# Primjenjena_II.net
KiCad netlist of a schematic drawn in Altium Designer
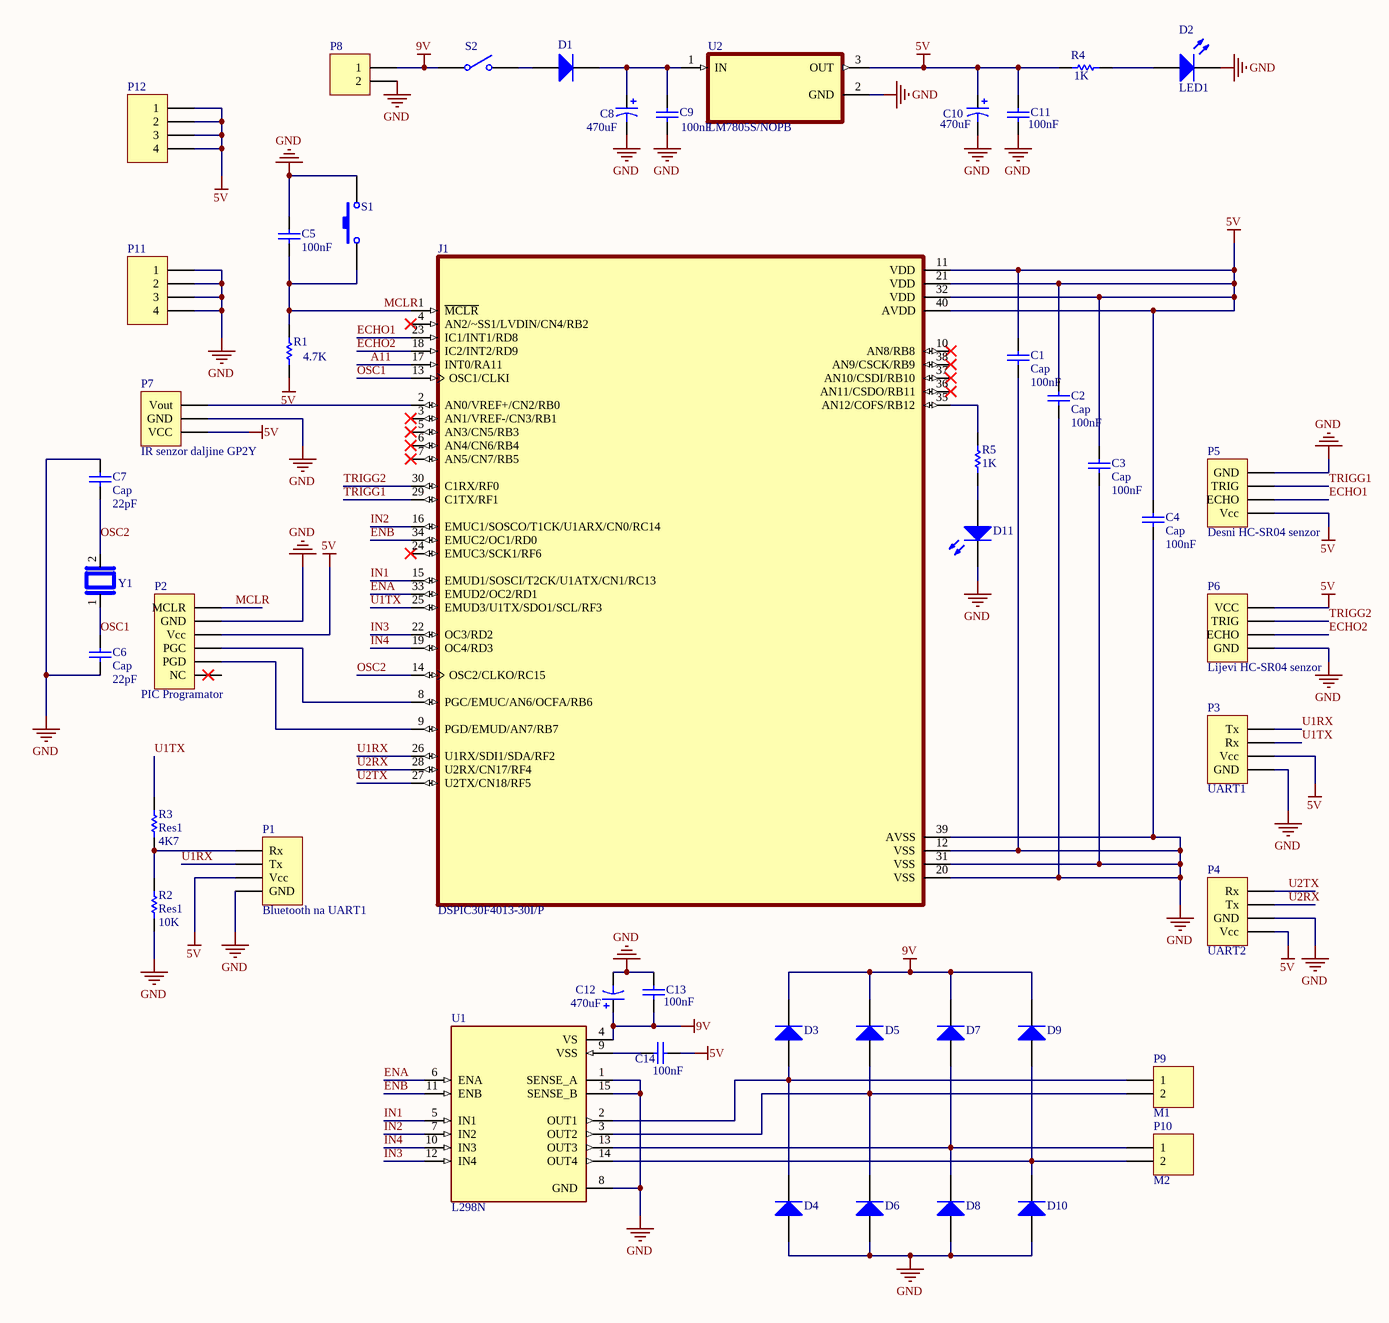
[diagram p0: Primjenjena_II.SchDoc]

(export (version "E")
  (design (tool "Eeschema 10.0.6"))
  (components
    (comp (ref "C1")
      (value "Cap")
      (footprint "RAD-0.1")
      (description "Capacitor")
      (fields (field (name "ALTIUM_VALUE") "100nF") (field (name "PUBLISHER") "Altium Limited"))
      (libsource (lib "Miscellaneous Devices") (part "Cap"))
    )
    (comp (ref "C2")
      (value "Cap")
      (footprint "RAD-0.1")
      (description "Capacitor")
      (fields (field (name "ALTIUM_VALUE") "100nF") (field (name "PUBLISHER") "Altium Limited"))
      (libsource (lib "Miscellaneous Devices") (part "Cap"))
    )
    (comp (ref "C3")
      (value "Cap")
      (footprint "RAD-0.1")
      (description "Capacitor")
      (fields (field (name "ALTIUM_VALUE") "100nF") (field (name "PUBLISHER") "Altium Limited"))
      (libsource (lib "Miscellaneous Devices") (part "Cap"))
    )
    (comp (ref "C4")
      (value "Cap")
      (footprint "RAD-0.1")
      (description "Capacitor")
      (fields (field (name "ALTIUM_VALUE") "100nF") (field (name "PUBLISHER") "Altium Limited"))
      (libsource (lib "Miscellaneous Devices") (part "Cap"))
    )
    (comp (ref "C5")
      (value "100nF")
      (footprint "RAD-0.1")
      (description "Capacitor")
      (fields (field (name "Comment") "Cap") (field (name "PUBLISHER") "Altium Limited"))
      (libsource (lib "Miscellaneous Devices") (part "Cap"))
    )
    (comp (ref "C6")
      (value "Cap")
      (footprint "RAD-0.1")
      (description "Capacitor")
      (fields (field (name "ALTIUM_VALUE") "22pF") (field (name "PUBLISHER") "Altium Limited"))
      (libsource (lib "Miscellaneous Devices") (part "Cap"))
    )
    (comp (ref "C7")
      (value "Cap")
      (footprint "RAD-0.1")
      (description "Capacitor")
      (fields (field (name "ALTIUM_VALUE") "22pF") (field (name "PUBLISHER") "Altium Limited"))
      (libsource (lib "Miscellaneous Devices") (part "Cap"))
    )
    (comp (ref "C8")
      (value "470uF")
      (footprint "Elektrolitski kondenzator")
      (description "Polarized Capacitor (Radial)")
      (fields (field (name "Comment") "Cap Pol1") (field (name "PUBLISHER") "Altium Limited"))
      (libsource (lib "Miscellaneous Devices") (part "Cap Pol1"))
    )
    (comp (ref "C9")
      (value "100nF")
      (footprint "RAD-0.1")
      (description "Capacitor")
      (fields (field (name "Comment") "Cap") (field (name "PUBLISHER") "Altium Limited"))
      (libsource (lib "Miscellaneous Devices") (part "Cap"))
    )
    (comp (ref "C10")
      (value "470uF")
      (footprint "Elektrolitski kondenzator")
      (description "Polarized Capacitor (Radial)")
      (fields (field (name "Comment") "Cap Pol1") (field (name "PUBLISHER") "Altium Limited"))
      (libsource (lib "Miscellaneous Devices") (part "Cap Pol1"))
    )
    (comp (ref "C11")
      (value "100nF")
      (footprint "RAD-0.1")
      (description "Capacitor")
      (fields (field (name "Comment") "Cap") (field (name "PUBLISHER") "Altium Limited"))
      (libsource (lib "Miscellaneous Devices") (part "Cap"))
    )
    (comp (ref "C12")
      (value "470uF")
      (footprint "Elektrolitski kondenzator")
      (description "Polarized Capacitor (Radial)")
      (fields (field (name "Comment") "Cap Pol1") (field (name "PUBLISHER") "Altium Limited"))
      (libsource (lib "Miscellaneous Devices") (part "Cap Pol1"))
    )
    (comp (ref "C13")
      (value "100nF")
      (footprint "RAD-0.1")
      (description "Capacitor")
      (fields (field (name "Comment") "Cap") (field (name "PUBLISHER") "Altium Limited"))
      (libsource (lib "Miscellaneous Devices") (part "Cap"))
    )
    (comp (ref "C14")
      (value "100nF")
      (footprint "RAD-0.1")
      (description "Capacitor")
      (fields (field (name "Comment") "Cap") (field (name "PUBLISHER") "Altium Limited"))
      (libsource (lib "Miscellaneous Devices") (part "Cap"))
    )
    (comp (ref "D1")
      (value "Diode 1N4007")
      (footprint "DO-41")
      (description "1 Amp General Purpose Rectifier")
      (fields (field (name "PUBLISHER") "Altium Limited"))
      (libsource (lib "Miscellaneous Devices") (part "Diode 1N4007"))
    )
    (comp (ref "D2")
      (value "LED1")
      (footprint "Diode")
      (description "Typical RED GaAs LED")
      (fields (field (name "PUBLISHER") "Altium Limited"))
      (libsource (lib "Miscellaneous Devices") (part "LED1"))
    )
    (comp (ref "D3")
      (value "Diode")
      (footprint "DO-41")
      (description "Default Diode")
      (fields (field (name "PUBLISHER") "Altium Limited"))
      (libsource (lib "Miscellaneous Devices") (part "Diode"))
    )
    (comp (ref "D4")
      (value "Diode")
      (footprint "DO-41")
      (description "Default Diode")
      (fields (field (name "PUBLISHER") "Altium Limited"))
      (libsource (lib "Miscellaneous Devices") (part "Diode"))
    )
    (comp (ref "D5")
      (value "Diode")
      (footprint "DO-41")
      (description "Default Diode")
      (fields (field (name "PUBLISHER") "Altium Limited"))
      (libsource (lib "Miscellaneous Devices") (part "Diode"))
    )
    (comp (ref "D6")
      (value "Diode")
      (footprint "DO-41")
      (description "Default Diode")
      (fields (field (name "PUBLISHER") "Altium Limited"))
      (libsource (lib "Miscellaneous Devices") (part "Diode"))
    )
    (comp (ref "D7")
      (value "Diode")
      (footprint "DO-41")
      (description "Default Diode")
      (fields (field (name "PUBLISHER") "Altium Limited"))
      (libsource (lib "Miscellaneous Devices") (part "Diode"))
    )
    (comp (ref "D8")
      (value "Diode")
      (footprint "DO-41")
      (description "Default Diode")
      (fields (field (name "PUBLISHER") "Altium Limited"))
      (libsource (lib "Miscellaneous Devices") (part "Diode"))
    )
    (comp (ref "D9")
      (value "Diode")
      (footprint "DO-41")
      (description "Default Diode")
      (fields (field (name "PUBLISHER") "Altium Limited"))
      (libsource (lib "Miscellaneous Devices") (part "Diode"))
    )
    (comp (ref "D10")
      (value "Diode")
      (footprint "DO-41")
      (description "Default Diode")
      (fields (field (name "PUBLISHER") "Altium Limited"))
      (libsource (lib "Miscellaneous Devices") (part "Diode"))
    )
    (comp (ref "D11")
      (value "LED1")
      (footprint "Diode")
      (description "Typical RED GaAs LED")
      (fields (field (name "PUBLISHER") "Altium Limited"))
      (libsource (lib "Miscellaneous Devices") (part "LED1"))
    )
    (comp (ref "J1")
      (value "DSPIC30F4013-30I/P")
      (footprint "DIP254P1524X482-40")
      (description "Digital Signal Processors, DSP, DSC General Purpose ¦ Microchip Technology Inc. DSPIC30F4013-30I/P")
      (fields (field (name "MF") "Microchip"))
      (libsource (lib "DSPIC30F4013-30I_P") (part "DSPIC30F4013-30I/P"))
    )
    (comp (ref "P1")
      (value "Bluetooth na UART1")
      (footprint "HDR1X4")
      (description "Header, 4-Pin")
      (fields (field (name "PUBLISHER") "Altium Limited"))
      (libsource (lib "") (part "Header 4_1"))
    )
    (comp (ref "P2")
      (value "PIC Programator")
      (footprint "HDR1X6")
      (description "Header, 6-Pin")
      (fields (field (name "PUBLISHER") "Altium Limited"))
      (libsource (lib "Miscellaneous Connectors") (part "Header 6"))
    )
    (comp (ref "P3")
      (value "UART1")
      (footprint "HDR1X4")
      (description "Header, 4-Pin")
      (fields (field (name "PUBLISHER") "Altium Limited"))
      (libsource (lib "Miscellaneous Connectors") (part "Header 4"))
    )
    (comp (ref "P4")
      (value "UART2")
      (footprint "HDR1X4")
      (description "Header, 4-Pin")
      (fields (field (name "PUBLISHER") "Altium Limited"))
      (libsource (lib "Miscellaneous Connectors") (part "Header 4"))
    )
    (comp (ref "P5")
      (value "Desni HC-SR04 senzor")
      (footprint "HDR1X4")
      (description "Header, 4-Pin")
      (fields (field (name "PUBLISHER") "Altium Limited"))
      (libsource (lib "Miscellaneous Connectors") (part "Header 4"))
    )
    (comp (ref "P6")
      (value "Lijevi HC-SR04 senzor")
      (footprint "HDR1X4")
      (description "Header, 4-Pin")
      (fields (field (name "PUBLISHER") "Altium Limited"))
      (libsource (lib "Miscellaneous Connectors") (part "Header 4"))
    )
    (comp (ref "P7")
      (value "IR senzor daljine GP2Y")
      (footprint "HDR1X3")
      (description "Header, 3-Pin")
      (fields (field (name "PUBLISHER") "Altium Limited"))
      (libsource (lib "Miscellaneous Connectors") (part "Header 3"))
    )
    (comp (ref "P8")
      (value "Header 2")
      (footprint "HDR1X2")
      (description "Header, 2-Pin")
      (fields (field (name "PUBLISHER") "Altium Limited"))
      (libsource (lib "") (part "Header 2_1"))
    )
    (comp (ref "P9")
      (value "M1")
      (footprint "HDR1X2")
      (description "Header, 2-Pin")
      (fields (field (name "PUBLISHER") "Altium Limited"))
      (libsource (lib "Miscellaneous Connectors") (part "Header 2"))
    )
    (comp (ref "P10")
      (value "M2")
      (footprint "HDR1X2")
      (description "Header, 2-Pin")
      (fields (field (name "PUBLISHER") "Altium Limited"))
      (libsource (lib "Miscellaneous Connectors") (part "Header 2"))
    )
    (comp (ref "P11")
      (value "Header 4")
      (footprint "HDR1X4")
      (description "Header, 4-Pin")
      (fields (field (name "PUBLISHER") "Altium Limited"))
      (libsource (lib "Miscellaneous Connectors") (part "Header 4"))
    )
    (comp (ref "P12")
      (value "Header 4")
      (footprint "HDR1X4")
      (description "Header, 4-Pin")
      (fields (field (name "PUBLISHER") "Altium Limited"))
      (libsource (lib "Miscellaneous Connectors") (part "Header 4"))
    )
    (comp (ref "R1")
      (value "4.7K")
      (footprint "AXIAL-0.3")
      (description "Resistor")
      (fields (field (name "Comment") "Res1") (field (name "PUBLISHER") "Altium Limited"))
      (libsource (lib "Miscellaneous Devices") (part "Res1"))
    )
    (comp (ref "R2")
      (value "Res1")
      (footprint "AXIAL-0.3")
      (description "Resistor")
      (fields (field (name "ALTIUM_VALUE") "10K") (field (name "PUBLISHER") "Altium Limited"))
      (libsource (lib "Miscellaneous Devices") (part "Res1"))
    )
    (comp (ref "R3")
      (value "Res1")
      (footprint "AXIAL-0.3")
      (description "Resistor")
      (fields (field (name "ALTIUM_VALUE") "4K7") (field (name "PUBLISHER") "Altium Limited"))
      (libsource (lib "Miscellaneous Devices") (part "Res1"))
    )
    (comp (ref "R4")
      (value "1K")
      (footprint "AXIAL-0.3")
      (description "Resistor")
      (fields (field (name "Comment") "Res1") (field (name "PUBLISHER") "Altium Limited"))
      (libsource (lib "Miscellaneous Devices") (part "Res1"))
    )
    (comp (ref "R5")
      (value "1K")
      (footprint "AXIAL-0.3")
      (description "Resistor")
      (fields (field (name "Comment") "Res1") (field (name "PUBLISHER") "Altium Limited"))
      (libsource (lib "Miscellaneous Devices") (part "Res1"))
    )
    (comp (ref "S1")
      (value "SW-PB")
      (footprint "SPST-2")
      (description "Switch")
      (fields (field (name "PUBLISHER") "Altium Limited"))
      (libsource (lib "Miscellaneous Devices") (part "SW-PB"))
    )
    (comp (ref "S2")
      (value "SW-SPST")
      (footprint "SPST-2")
      (description "Single-Pole, Single-Throw Switch")
      (fields (field (name "PUBLISHER") "Altium Limited"))
      (libsource (lib "Miscellaneous Devices") (part "SW-SPST"))
    )
    (comp (ref "U1")
      (value "L298N")
      (footprint "TO127P2020X500X2100-15")
      (description "Dual Full Bridge Motor Driver 15-Pin(15+Tab) MULTIWATT V Tube")
      (libsource (lib "L298N") (part "L298N"))
    )
    (comp (ref "U2")
      (value "LM7805S/NOPB")
      (footprint "TO-220-AB")
      (description "1.5-A, 30-V, linear voltage regulator")
      (fields (field (name "MF") "Texas Instruments"))
      (libsource (lib "LM7805S_NOPB") (part "LM7805S/NOPB"))
    )
    (comp (ref "Y1")
      (value "HC-49/U-S16000000ABJB")
      (footprint "XTAL_HC49P488W43L1150T466H350")
      (description "16 MHz Â±30ppm Crystal 18pF 50 Ohms HC-49/US")
      (fields (field (name "MF") "Citizen Finedevice"))
      (libsource (lib "HC-49_U-S16000000ABJB") (part "HC-49/U-S16000000ABJB"))
    )
  )
  (nets
    (net (code "1") (name "/A11") (class "Default")
      (node (ref "J1") (pin "17") (pinfunction "INT0/RA11_17") (pintype "input"))
    )
    (net (code "2") (name "/ECHO1") (class "Default")
      (node (ref "J1") (pin "23") (pinfunction "IC1/INT1/RD8_23") (pintype "input"))
      (node (ref "P5") (pin "3") (pinfunction "3_3") (pintype "passive"))
    )
    (net (code "3") (name "/ECHO2") (class "Default")
      (node (ref "J1") (pin "18") (pinfunction "IC2/INT2/RD9_18") (pintype "input"))
      (node (ref "P6") (pin "3") (pinfunction "3_3") (pintype "passive"))
    )
    (net (code "4") (name "/ENA") (class "Default")
      (node (ref "J1") (pin "33") (pinfunction "EMUD2/OC2/RD1_33") (pintype "bidirectional"))
      (node (ref "U1") (pin "6") (pinfunction "ENA_6") (pintype "input"))
    )
    (net (code "5") (name "/ENB") (class "Default")
      (node (ref "J1") (pin "34") (pinfunction "EMUC2/OC1/RD0_34") (pintype "bidirectional"))
      (node (ref "U1") (pin "11") (pinfunction "ENB_11") (pintype "input"))
    )
    (net (code "6") (name "/IN1") (class "Default")
      (node (ref "J1") (pin "15") (pinfunction "EMUD1/SOSCI/T2CK/U1ATX/CN1/RC13_15") (pintype "bidirectional"))
      (node (ref "U1") (pin "5") (pinfunction "IN1_5") (pintype "input"))
    )
    (net (code "7") (name "/IN2") (class "Default")
      (node (ref "J1") (pin "16") (pinfunction "EMUC1/SOSCO/T1CK/U1ARX/CN0/RC14_16") (pintype "bidirectional"))
      (node (ref "U1") (pin "7") (pinfunction "IN2_7") (pintype "input"))
    )
    (net (code "8") (name "/IN3") (class "Default")
      (node (ref "J1") (pin "22") (pinfunction "OC3/RD2_22") (pintype "bidirectional"))
      (node (ref "U1") (pin "12") (pinfunction "IN4_12") (pintype "input"))
    )
    (net (code "9") (name "/IN4") (class "Default")
      (node (ref "J1") (pin "19") (pinfunction "OC4/RD3_19") (pintype "bidirectional"))
      (node (ref "U1") (pin "10") (pinfunction "IN3_10") (pintype "input"))
    )
    (net (code "10") (name "/MCLR") (class "Default")
      (node (ref "C5") (pin "1") (pinfunction "1_1") (pintype "passive"))
      (node (ref "J1") (pin "1") (pinfunction "~{MCLR}_1") (pintype "input"))
      (node (ref "P2") (pin "1") (pinfunction "MCLR_1") (pintype "passive"))
      (node (ref "R1") (pin "2") (pinfunction "2_2") (pintype "passive"))
      (node (ref "S1") (pin "1") (pinfunction "1_1") (pintype "passive"))
    )
    (net (code "11") (name "/OSC1") (class "Default")
      (node (ref "C6") (pin "2") (pinfunction "2_2") (pintype "passive"))
      (node (ref "J1") (pin "13") (pinfunction "OSC1/CLKI_13") (pintype "input"))
      (node (ref "Y1") (pin "1") (pinfunction "1_1") (pintype "passive"))
    )
    (net (code "12") (name "/OSC2") (class "Default")
      (node (ref "C7") (pin "1") (pinfunction "1_1") (pintype "passive"))
      (node (ref "J1") (pin "14") (pinfunction "OSC2/CLKO/RC15_14") (pintype "bidirectional"))
      (node (ref "Y1") (pin "2") (pinfunction "2_2") (pintype "passive"))
    )
    (net (code "13") (name "/TRIGG1") (class "Default")
      (node (ref "J1") (pin "29") (pinfunction "C1TX/RF1_29") (pintype "bidirectional"))
      (node (ref "P5") (pin "2") (pinfunction "2_2") (pintype "passive"))
    )
    (net (code "14") (name "/TRIGG2") (class "Default")
      (node (ref "J1") (pin "30") (pinfunction "C1RX/RF0_30") (pintype "bidirectional"))
      (node (ref "P6") (pin "2") (pinfunction "2_2") (pintype "passive"))
    )
    (net (code "15") (name "/U1RX") (class "Default")
      (node (ref "J1") (pin "26") (pinfunction "U1RX/SDI1/SDA/RF2_26") (pintype "bidirectional"))
      (node (ref "P1") (pin "2") (pinfunction "Tx_2") (pintype "passive"))
      (node (ref "P3") (pin "1") (pinfunction "1_1") (pintype "passive"))
    )
    (net (code "16") (name "/U1TX") (class "Default")
      (node (ref "J1") (pin "25") (pinfunction "EMUD3/U1TX/SDO1/SCL/RF3_25") (pintype "bidirectional"))
      (node (ref "P3") (pin "2") (pinfunction "2_2") (pintype "passive"))
      (node (ref "R3") (pin "2") (pinfunction "2_2") (pintype "passive"))
    )
    (net (code "17") (name "/U2RX") (class "Default")
      (node (ref "J1") (pin "28") (pinfunction "U2RX/CN17/RF4_28") (pintype "bidirectional"))
      (node (ref "P4") (pin "2") (pinfunction "2_2") (pintype "passive"))
    )
    (net (code "18") (name "/U2TX") (class "Default")
      (node (ref "J1") (pin "27") (pinfunction "U2TX/CN18/RF5_27") (pintype "bidirectional"))
      (node (ref "P4") (pin "1") (pinfunction "1_1") (pintype "passive"))
    )
    (net (code "19") (name "5V") (class "Default")
      (node (ref "C1") (pin "2") (pinfunction "2_2") (pintype "passive"))
      (node (ref "C10") (pin "1") (pinfunction "1_1") (pintype "passive"))
      (node (ref "C11") (pin "2") (pinfunction "2_2") (pintype "passive"))
      (node (ref "C14") (pin "1") (pinfunction "1_1") (pintype "passive"))
      (node (ref "C2") (pin "2") (pinfunction "2_2") (pintype "passive"))
      (node (ref "C3") (pin "2") (pinfunction "2_2") (pintype "passive"))
      (node (ref "C4") (pin "2") (pinfunction "2_2") (pintype "passive"))
      (node (ref "J1") (pin "11") (pinfunction "VDD_11") (pintype "power_in"))
      (node (ref "J1") (pin "21") (pinfunction "VDD_21") (pintype "power_in"))
      (node (ref "J1") (pin "32") (pinfunction "VDD_32") (pintype "power_in"))
      (node (ref "J1") (pin "40") (pinfunction "AVDD_40") (pintype "power_in"))
      (node (ref "P1") (pin "3") (pinfunction "Vcc_3") (pintype "passive"))
      (node (ref "P12") (pin "1") (pinfunction "1_1") (pintype "passive"))
      (node (ref "P12") (pin "2") (pinfunction "2_2") (pintype "passive"))
      (node (ref "P12") (pin "3") (pinfunction "3_3") (pintype "passive"))
      (node (ref "P12") (pin "4") (pinfunction "4_4") (pintype "passive"))
      (node (ref "P2") (pin "3") (pinfunction "Vcc_3") (pintype "passive"))
      (node (ref "P3") (pin "3") (pinfunction "3_3") (pintype "passive"))
      (node (ref "P4") (pin "4") (pinfunction "4_4") (pintype "passive"))
      (node (ref "P5") (pin "4") (pinfunction "4_4") (pintype "passive"))
      (node (ref "P6") (pin "1") (pinfunction "1_1") (pintype "passive"))
      (node (ref "P7") (pin "3") (pinfunction "VCC_3") (pintype "passive"))
      (node (ref "R1") (pin "1") (pinfunction "1_1") (pintype "passive"))
      (node (ref "R4") (pin "1") (pinfunction "1_1") (pintype "passive"))
      (node (ref "U2") (pin "3") (pinfunction "OUT_3") (pintype "output"))
    )
    (net (code "20") (name "9V") (class "Default")
      (node (ref "C12") (pin "1") (pinfunction "1_1") (pintype "passive"))
      (node (ref "C13") (pin "1") (pinfunction "1_1") (pintype "passive"))
      (node (ref "D3") (pin "2") (pinfunction "K_2") (pintype "passive"))
      (node (ref "D5") (pin "2") (pinfunction "K_2") (pintype "passive"))
      (node (ref "D7") (pin "2") (pinfunction "K_2") (pintype "passive"))
      (node (ref "D9") (pin "2") (pinfunction "K_2") (pintype "passive"))
      (node (ref "P8") (pin "1") (pinfunction "1_1") (pintype "passive"))
      (node (ref "S2") (pin "1") (pinfunction "COMMON_1") (pintype "passive"))
      (node (ref "U1") (pin "4") (pinfunction "VS_4") (pintype "power_in"))
    )
    (net (code "21") (name "GND") (class "Default")
      (node (ref "C1") (pin "1") (pinfunction "1_1") (pintype "passive"))
      (node (ref "C10") (pin "2") (pinfunction "2_2") (pintype "passive"))
      (node (ref "C11") (pin "1") (pinfunction "1_1") (pintype "passive"))
      (node (ref "C12") (pin "2") (pinfunction "2_2") (pintype "passive"))
      (node (ref "C13") (pin "2") (pinfunction "2_2") (pintype "passive"))
      (node (ref "C2") (pin "1") (pinfunction "1_1") (pintype "passive"))
      (node (ref "C3") (pin "1") (pinfunction "1_1") (pintype "passive"))
      (node (ref "C4") (pin "1") (pinfunction "1_1") (pintype "passive"))
      (node (ref "C5") (pin "2") (pinfunction "2_2") (pintype "passive"))
      (node (ref "C6") (pin "1") (pinfunction "1_1") (pintype "passive"))
      (node (ref "C7") (pin "2") (pinfunction "2_2") (pintype "passive"))
      (node (ref "C8") (pin "2") (pinfunction "2_2") (pintype "passive"))
      (node (ref "C9") (pin "1") (pinfunction "1_1") (pintype "passive"))
      (node (ref "D10") (pin "1") (pinfunction "A_1") (pintype "passive"))
      (node (ref "D11") (pin "2") (pinfunction "K_2") (pintype "passive"))
      (node (ref "D2") (pin "2") (pinfunction "K_2") (pintype "passive"))
      (node (ref "D4") (pin "1") (pinfunction "A_1") (pintype "passive"))
      (node (ref "D6") (pin "1") (pinfunction "A_1") (pintype "passive"))
      (node (ref "D8") (pin "1") (pinfunction "A_1") (pintype "passive"))
      (node (ref "J1") (pin "12") (pinfunction "VSS_12") (pintype "power_in"))
      (node (ref "J1") (pin "20") (pinfunction "VSS_20") (pintype "power_in"))
      (node (ref "J1") (pin "31") (pinfunction "VSS_31") (pintype "power_in"))
      (node (ref "J1") (pin "39") (pinfunction "AVSS_39") (pintype "power_in"))
      (node (ref "P1") (pin "4") (pinfunction "GND_4") (pintype "passive"))
      (node (ref "P11") (pin "1") (pinfunction "1_1") (pintype "passive"))
      (node (ref "P11") (pin "2") (pinfunction "2_2") (pintype "passive"))
      (node (ref "P11") (pin "3") (pinfunction "3_3") (pintype "passive"))
      (node (ref "P11") (pin "4") (pinfunction "4_4") (pintype "passive"))
      (node (ref "P2") (pin "2") (pinfunction "GND_2") (pintype "passive"))
      (node (ref "P3") (pin "4") (pinfunction "4_4") (pintype "passive"))
      (node (ref "P4") (pin "3") (pinfunction "3_3") (pintype "passive"))
      (node (ref "P5") (pin "1") (pinfunction "1_1") (pintype "passive"))
      (node (ref "P6") (pin "4") (pinfunction "4_4") (pintype "passive"))
      (node (ref "P7") (pin "2") (pinfunction "GND_2") (pintype "passive"))
      (node (ref "P8") (pin "2") (pinfunction "2_2") (pintype "passive"))
      (node (ref "R2") (pin "1") (pinfunction "1_1") (pintype "passive"))
      (node (ref "S1") (pin "2") (pinfunction "2_2") (pintype "passive"))
      (node (ref "U1") (pin "1") (pinfunction "SENSE_A_1") (pintype "passive"))
      (node (ref "U1") (pin "15") (pinfunction "SENSE_B_15") (pintype "passive"))
      (node (ref "U1") (pin "8") (pinfunction "GND_8") (pintype "power_in"))
      (node (ref "U2") (pin "2") (pinfunction "GND_2") (pintype "power_in"))
    )
    (net (code "22") (name "Net-(D1-A)") (class "Default")
      (node (ref "D1") (pin "1") (pinfunction "A_1") (pintype "passive"))
      (node (ref "S2") (pin "2") (pinfunction "NO_2") (pintype "passive"))
    )
    (net (code "23") (name "Net-(D1-K)") (class "Default")
      (node (ref "C8") (pin "1") (pinfunction "1_1") (pintype "passive"))
      (node (ref "C9") (pin "2") (pinfunction "2_2") (pintype "passive"))
      (node (ref "D1") (pin "2") (pinfunction "K_2") (pintype "passive"))
      (node (ref "U2") (pin "1") (pinfunction "IN_1") (pintype "input"))
    )
    (net (code "24") (name "Net-(D2-A)") (class "Default")
      (node (ref "D2") (pin "1") (pinfunction "A_1") (pintype "passive"))
      (node (ref "R4") (pin "2") (pinfunction "2_2") (pintype "passive"))
    )
    (net (code "25") (name "Net-(D3-A)") (class "Default")
      (node (ref "D3") (pin "1") (pinfunction "A_1") (pintype "passive"))
      (node (ref "D4") (pin "2") (pinfunction "K_2") (pintype "passive"))
      (node (ref "P9") (pin "1") (pinfunction "1_1") (pintype "passive"))
      (node (ref "U1") (pin "2") (pinfunction "OUT1_2") (pintype "output"))
    )
    (net (code "26") (name "Net-(D5-A)") (class "Default")
      (node (ref "D5") (pin "1") (pinfunction "A_1") (pintype "passive"))
      (node (ref "D6") (pin "2") (pinfunction "K_2") (pintype "passive"))
      (node (ref "P9") (pin "2") (pinfunction "2_2") (pintype "passive"))
      (node (ref "U1") (pin "3") (pinfunction "OUT2_3") (pintype "output"))
    )
    (net (code "27") (name "Net-(D7-A)") (class "Default")
      (node (ref "D7") (pin "1") (pinfunction "A_1") (pintype "passive"))
      (node (ref "D8") (pin "2") (pinfunction "K_2") (pintype "passive"))
      (node (ref "P10") (pin "1") (pinfunction "1_1") (pintype "passive"))
      (node (ref "U1") (pin "13") (pinfunction "OUT3_13") (pintype "output"))
    )
    (net (code "28") (name "Net-(D10-K)") (class "Default")
      (node (ref "D10") (pin "2") (pinfunction "K_2") (pintype "passive"))
      (node (ref "D9") (pin "1") (pinfunction "A_1") (pintype "passive"))
      (node (ref "P10") (pin "2") (pinfunction "2_2") (pintype "passive"))
      (node (ref "U1") (pin "14") (pinfunction "OUT4_14") (pintype "output"))
    )
    (net (code "29") (name "Net-(D11-A)") (class "Default")
      (node (ref "D11") (pin "1") (pinfunction "A_1") (pintype "passive"))
      (node (ref "R5") (pin "1") (pinfunction "1_1") (pintype "passive"))
    )
    (net (code "30") (name "Net-(J1-AN0{slash}VREF+{slash}CN2{slash}RB0)") (class "Default")
      (node (ref "J1") (pin "2") (pinfunction "AN0/VREF+/CN2/RB0_2") (pintype "bidirectional"))
      (node (ref "P7") (pin "1") (pinfunction "Vout_1") (pintype "passive"))
    )
    (net (code "31") (name "Net-(J1-AN12{slash}COFS{slash}RB12)") (class "Default")
      (node (ref "J1") (pin "35") (pinfunction "AN12/COFS/RB12_35") (pintype "bidirectional"))
      (node (ref "R5") (pin "2") (pinfunction "2_2") (pintype "passive"))
    )
    (net (code "32") (name "Net-(J1-PGC{slash}EMUC{slash}AN6{slash}OCFA{slash}RB6)") (class "Default")
      (node (ref "J1") (pin "8") (pinfunction "PGC/EMUC/AN6/OCFA/RB6_8") (pintype "bidirectional"))
      (node (ref "P2") (pin "4") (pinfunction "PGC_4") (pintype "passive"))
    )
    (net (code "33") (name "Net-(J1-PGD{slash}EMUD{slash}AN7{slash}RB7)") (class "Default")
      (node (ref "J1") (pin "9") (pinfunction "PGD/EMUD/AN7/RB7_9") (pintype "bidirectional"))
      (node (ref "P2") (pin "5") (pinfunction "PGD_5") (pintype "passive"))
    )
    (net (code "34") (name "Net-(P1-Rx)") (class "Default")
      (node (ref "P1") (pin "1") (pinfunction "Rx_1") (pintype "passive"))
      (node (ref "R2") (pin "2") (pinfunction "2_2") (pintype "passive"))
      (node (ref "R3") (pin "1") (pinfunction "1_1") (pintype "passive"))
    )
    (net (code "35") (name "Net-(U1-VSS)") (class "Default")
      (node (ref "C14") (pin "2") (pinfunction "2_2") (pintype "passive"))
      (node (ref "U1") (pin "9") (pinfunction "VSS_9") (pintype "input"))
    )
    (net (code "36") (name "unconnected-(J1-AN1{slash}VREF-{slash}CN3{slash}RB1-Pad3)") (class "Default")
      (node (ref "J1") (pin "3") (pinfunction "AN1/VREF-/CN3/RB1_3") (pintype "bidirectional+no_connect"))
    )
    (net (code "37") (name "unconnected-(J1-AN2{slash}~SS1{slash}LVDIN{slash}CN4{slash}RB2-Pad4)") (class "Default")
      (node (ref "J1") (pin "4") (pinfunction "AN2/~SS1/LVDIN/CN4/RB2_4") (pintype "input+no_connect"))
    )
    (net (code "38") (name "unconnected-(J1-AN3{slash}CN5{slash}RB3-Pad5)") (class "Default")
      (node (ref "J1") (pin "5") (pinfunction "AN3/CN5/RB3_5") (pintype "bidirectional+no_connect"))
    )
    (net (code "39") (name "unconnected-(J1-AN4{slash}CN6{slash}RB4-Pad6)") (class "Default")
      (node (ref "J1") (pin "6") (pinfunction "AN4/CN6/RB4_6") (pintype "bidirectional+no_connect"))
    )
    (net (code "40") (name "unconnected-(J1-AN5{slash}CN7{slash}RB5-Pad7)") (class "Default")
      (node (ref "J1") (pin "7") (pinfunction "AN5/CN7/RB5_7") (pintype "bidirectional+no_connect"))
    )
    (net (code "41") (name "unconnected-(J1-AN8{slash}RB8-Pad10)") (class "Default")
      (node (ref "J1") (pin "10") (pinfunction "AN8/RB8_10") (pintype "bidirectional+no_connect"))
    )
    (net (code "42") (name "unconnected-(J1-AN9{slash}CSCK{slash}RB9-Pad38)") (class "Default")
      (node (ref "J1") (pin "38") (pinfunction "AN9/CSCK/RB9_38") (pintype "bidirectional+no_connect"))
    )
    (net (code "43") (name "unconnected-(J1-AN10{slash}CSDI{slash}RB10-Pad37)") (class "Default")
      (node (ref "J1") (pin "37") (pinfunction "AN10/CSDI/RB10_37") (pintype "bidirectional+no_connect"))
    )
    (net (code "44") (name "unconnected-(J1-AN11{slash}CSDO{slash}RB11-Pad36)") (class "Default")
      (node (ref "J1") (pin "36") (pinfunction "AN11/CSDO/RB11_36") (pintype "bidirectional+no_connect"))
    )
    (net (code "45") (name "unconnected-(J1-EMUC3{slash}SCK1{slash}RF6-Pad24)") (class "Default")
      (node (ref "J1") (pin "24") (pinfunction "EMUC3/SCK1/RF6_24") (pintype "bidirectional+no_connect"))
    )
    (net (code "46") (name "unconnected-(P2-NC-Pad6)") (class "Default")
      (node (ref "P2") (pin "6") (pinfunction "NC_6") (pintype "passive"))
    )
  )
)
